# nufsr-user-io.net
KiCad netlist of a schematic drawn in Altium Designer
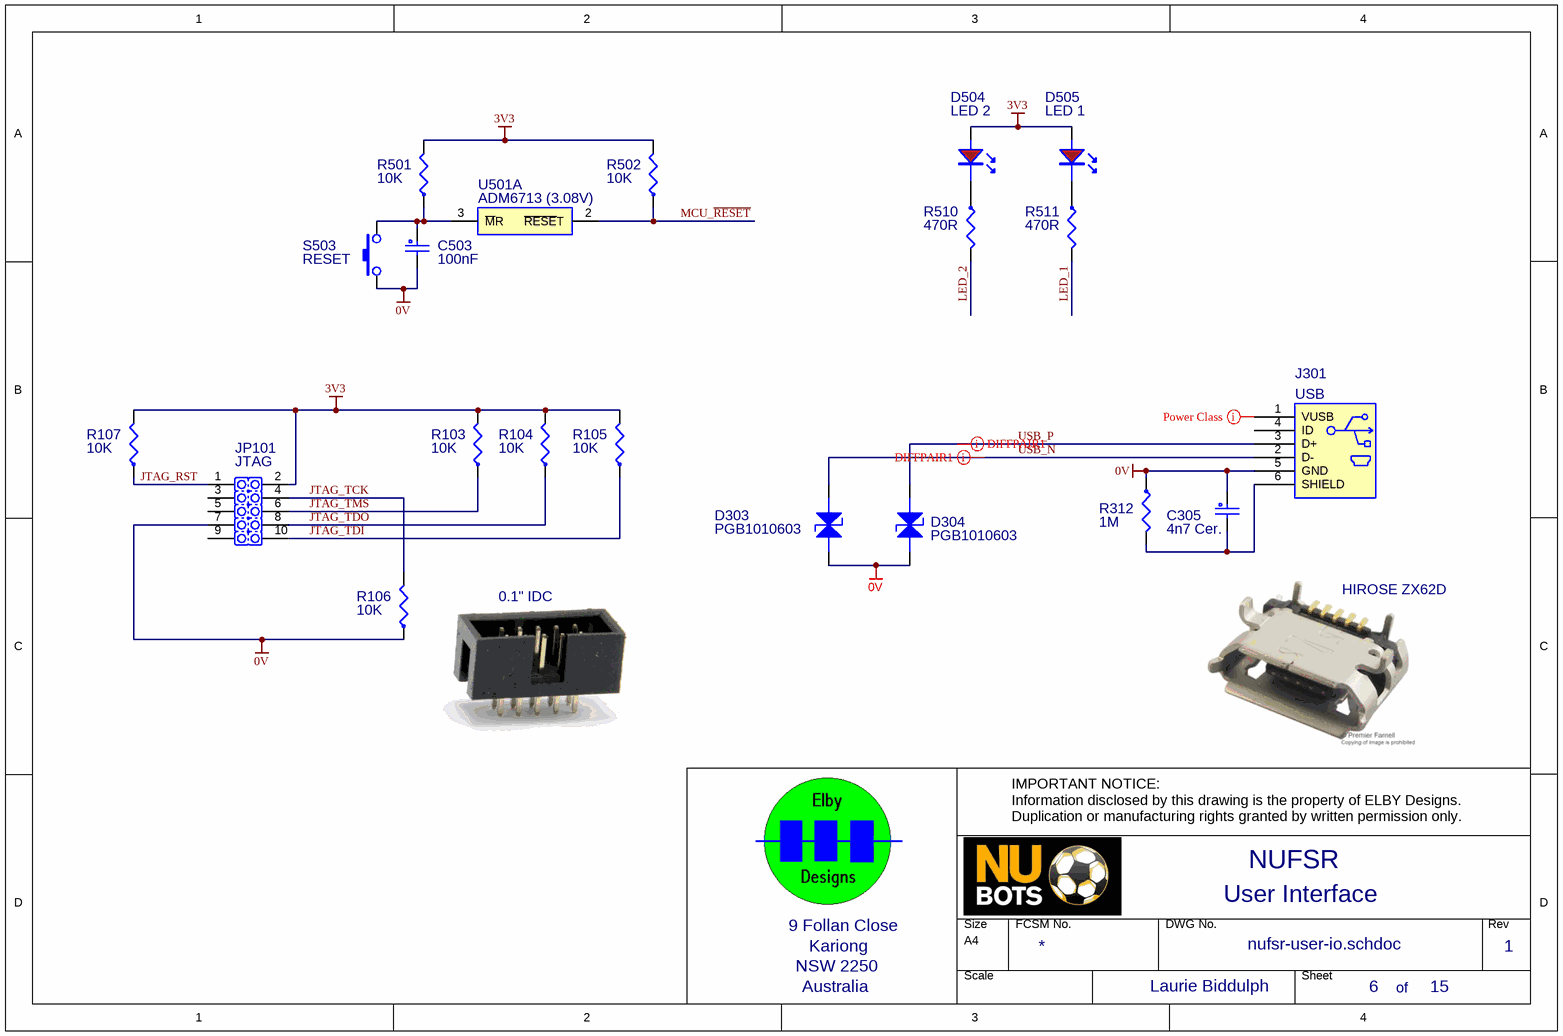
[diagram p0: nufsr-user-io.schdoc]

(export (version "E")
  (design (tool "Eeschema 10.0.6"))
  (components
    (comp (ref "C305")
      (value "4n7 Cer.")
      (footprint "0603(LB)")
      (description "4700pF NPO, 50VDC Ceramic Disc")
      (libsource (lib "capacitor") (part "CC-4700PF(LB)"))
    )
    (comp (ref "C503")
      (value "100nF")
      (footprint "0603(LB)")
      (description "Monolithic Ceramic")
      (libsource (lib "capacitor") (part "CC-100NF(LB)"))
    )
    (comp (ref "D303")
      (value "PGB1010603")
      (footprint "0603(LB)")
      (description "500V Pulse-Guard")
      (libsource (lib "NuBots") (part "PGB1010603"))
    )
    (comp (ref "D304")
      (value "PGB1010603")
      (footprint "0603(LB)")
      (description "500V Pulse-Guard")
      (libsource (lib "NuBots") (part "PGB1010603"))
    )
    (comp (ref "D504")
      (value "LED 2")
      (footprint "LED-0603(LB)")
      (description "LED")
      (libsource (lib "semi") (part "LED-RED(LB)"))
    )
    (comp (ref "D505")
      (value "LED 1")
      (footprint "LED-0603(LB)")
      (description "LED")
      (libsource (lib "semi") (part "LED-RED(LB)"))
    )
    (comp (ref "J301") (value "USB") (footprint "USB-ZX62D") (libsource (lib "NuBots") (part "ZX62D-B-5P8")))
    (comp (ref "JP101")
      (value "JTAG")
      (footprint "HDR2X5(LB)")
      (description "Connector")
      (libsource (lib "connectors") (part "HDR2X5(LB)"))
    )
    (comp (ref "R103")
      (value "10K")
      (footprint "0603(LB)")
      (description "0.5W 1% Metal Film Resistor")
      (libsource (lib "resistor") (part "RM-10K(LB)"))
    )
    (comp (ref "R104")
      (value "10K")
      (footprint "0603(LB)")
      (description "0.5W 1% Metal Film Resistor")
      (libsource (lib "resistor") (part "RM-10K(LB)"))
    )
    (comp (ref "R105")
      (value "10K")
      (footprint "0603(LB)")
      (description "0.5W 1% Metal Film Resistor")
      (libsource (lib "resistor") (part "RM-10K(LB)"))
    )
    (comp (ref "R106")
      (value "10K")
      (footprint "0603(LB)")
      (description "0.5W 1% Metal Film Resistor")
      (libsource (lib "resistor") (part "RM-10K(LB)"))
    )
    (comp (ref "R107")
      (value "10K")
      (footprint "0603(LB)")
      (description "0.5W 1% Metal Film Resistor")
      (libsource (lib "resistor") (part "RM-10K(LB)"))
    )
    (comp (ref "R312")
      (value "1M")
      (footprint "0603(LB)")
      (description "0.5W 1% Metal Film Resistor")
      (libsource (lib "resistor") (part "RM-1M(LB)"))
    )
    (comp (ref "R501")
      (value "10K")
      (footprint "0603(LB)")
      (description "0.5W 1% Metal Film Resistor")
      (libsource (lib "resistor") (part "RM-10K(LB)"))
    )
    (comp (ref "R502")
      (value "10K")
      (footprint "0603(LB)")
      (description "0.5W 1% Metal Film Resistor")
      (libsource (lib "resistor") (part "RM-10K(LB)"))
    )
    (comp (ref "R510")
      (value "470R")
      (footprint "0603(LB)")
      (description "0.5W 1% Metal Film Resistor")
      (libsource (lib "resistor") (part "RM-470R(LB)"))
    )
    (comp (ref "R511")
      (value "470R")
      (footprint "0603(LB)")
      (description "0.5W 1% Metal Film Resistor")
      (libsource (lib "resistor") (part "RM-470R(LB)"))
    )
    (comp (ref "S503")
      (value "RESET")
      (footprint "HDR1X2(LB)")
      (description "PCB Push-button Switch")
      (libsource (lib "switches") (part "SW-PB-SPST(LB)"))
    )
    (comp (ref "U501")
      (value "ADM6713 (3.08V)")
      (footprint "SC70-4")
      (description "Microprocessor Supervisory Circuit")
      (libsource (lib "NuBots") (part "ADM6713"))
    )
  )
  (nets
    (net (code "1") (name "/JTAG_RST") (class "Default")
      (node (ref "JP101") (pin "1") (pinfunction "1_1") (pintype "passive"))
      (node (ref "R107") (pin "1") (pinfunction "1_1") (pintype "passive"))
    )
    (net (code "2") (name "/JTAG_TCK") (class "Default")
      (node (ref "JP101") (pin "4") (pinfunction "4_4") (pintype "passive"))
      (node (ref "R106") (pin "2") (pinfunction "2_2") (pintype "passive"))
    )
    (net (code "3") (name "/JTAG_TDI") (class "Default")
      (node (ref "JP101") (pin "10") (pinfunction "10_10") (pintype "passive"))
      (node (ref "R105") (pin "1") (pinfunction "1_1") (pintype "passive"))
    )
    (net (code "4") (name "/JTAG_TDO") (class "Default")
      (node (ref "JP101") (pin "8") (pinfunction "8_8") (pintype "passive"))
      (node (ref "R104") (pin "1") (pinfunction "1_1") (pintype "passive"))
    )
    (net (code "5") (name "/JTAG_TMS") (class "Default")
      (node (ref "JP101") (pin "6") (pinfunction "6_6") (pintype "passive"))
      (node (ref "R103") (pin "1") (pinfunction "1_1") (pintype "passive"))
    )
    (net (code "6") (name "/LED_1") (class "Default")
      (node (ref "R511") (pin "2") (pinfunction "2_2") (pintype "passive"))
    )
    (net (code "7") (name "/LED_2") (class "Default")
      (node (ref "R510") (pin "2") (pinfunction "2_2") (pintype "passive"))
    )
    (net (code "8") (name "/MCU_~{RESET}") (class "Default")
      (node (ref "R502") (pin "1") (pinfunction "1_1") (pintype "passive"))
      (node (ref "U501") (pin "2") (pinfunction "~{RESE}T_2") (pintype "passive"))
    )
    (net (code "9") (name "/USB_N") (class "Default")
      (node (ref "D303") (pin "1") (pinfunction "1_1") (pintype "passive"))
      (node (ref "J301") (pin "2") (pinfunction "D-_2") (pintype "passive"))
    )
    (net (code "10") (name "/USB_P") (class "Default")
      (node (ref "D304") (pin "1") (pinfunction "1_1") (pintype "passive"))
      (node (ref "J301") (pin "3") (pinfunction "D+_3") (pintype "passive"))
    )
    (net (code "11") (name "0V") (class "Default")
      (node (ref "C305") (pin "1") (pintype "passive"))
      (node (ref "C503") (pin "2") (pintype "passive"))
      (node (ref "D303") (pin "2") (pinfunction "2_2") (pintype "passive"))
      (node (ref "D304") (pin "2") (pinfunction "2_2") (pintype "passive"))
      (node (ref "J301") (pin "5") (pinfunction "GND_5") (pintype "passive"))
      (node (ref "JP101") (pin "7") (pinfunction "7_7") (pintype "passive"))
      (node (ref "R106") (pin "1") (pinfunction "1_1") (pintype "passive"))
      (node (ref "R312") (pin "1") (pinfunction "1_1") (pintype "passive"))
      (node (ref "S503") (pin "1") (pinfunction "COM_1") (pintype "passive"))
    )
    (net (code "12") (name "3V3") (class "Default")
      (node (ref "D504") (pin "A") (pinfunction "A_A") (pintype "passive"))
      (node (ref "D505") (pin "A") (pinfunction "A_A") (pintype "passive"))
      (node (ref "JP101") (pin "2") (pinfunction "2_2") (pintype "passive"))
      (node (ref "R103") (pin "2") (pinfunction "2_2") (pintype "passive"))
      (node (ref "R104") (pin "2") (pinfunction "2_2") (pintype "passive"))
      (node (ref "R105") (pin "2") (pinfunction "2_2") (pintype "passive"))
      (node (ref "R107") (pin "2") (pinfunction "2_2") (pintype "passive"))
      (node (ref "R501") (pin "2") (pinfunction "2_2") (pintype "passive"))
      (node (ref "R502") (pin "2") (pinfunction "2_2") (pintype "passive"))
    )
    (net (code "13") (name "Net-(D504-PadK)") (class "Default")
      (node (ref "D504") (pin "K") (pinfunction "K_K") (pintype "passive"))
      (node (ref "R510") (pin "1") (pinfunction "1_1") (pintype "passive"))
    )
    (net (code "14") (name "Net-(D505-PadK)") (class "Default")
      (node (ref "D505") (pin "K") (pinfunction "K_K") (pintype "passive"))
      (node (ref "R511") (pin "1") (pinfunction "1_1") (pintype "passive"))
    )
    (net (code "15") (name "Net-(J301-SHIELD)") (class "Default")
      (node (ref "C305") (pin "2") (pintype "passive"))
      (node (ref "J301") (pin "6") (pinfunction "SHIELD_6") (pintype "passive"))
      (node (ref "R312") (pin "2") (pinfunction "2_2") (pintype "passive"))
    )
    (net (code "16") (name "Net-(S503-NO)") (class "Default")
      (node (ref "C503") (pin "1") (pintype "passive"))
      (node (ref "R501") (pin "1") (pinfunction "1_1") (pintype "passive"))
      (node (ref "S503") (pin "2") (pinfunction "NO_2") (pintype "passive"))
      (node (ref "U501") (pin "3") (pinfunction "~{M}R_3") (pintype "passive"))
    )
    (net (code "17") (name "unconnected-(J301-ID-Pad4)") (class "Default")
      (node (ref "J301") (pin "4") (pinfunction "ID_4") (pintype "passive"))
    )
    (net (code "18") (name "unconnected-(J301-VUSB-Pad1)") (class "Default")
      (node (ref "J301") (pin "1") (pinfunction "VUSB_1") (pintype "passive"))
    )
    (net (code "19") (name "unconnected-(JP101-Pad3)") (class "Default")
      (node (ref "JP101") (pin "3") (pinfunction "3_3") (pintype "passive"))
    )
    (net (code "20") (name "unconnected-(JP101-Pad5)") (class "Default")
      (node (ref "JP101") (pin "5") (pinfunction "5_5") (pintype "passive"))
    )
    (net (code "21") (name "unconnected-(JP101-Pad9)") (class "Default")
      (node (ref "JP101") (pin "9") (pinfunction "9_9") (pintype "passive"))
    )
  )
)
